# bd2_redraw.net
KiCad netlist of a schematic drawn in EAGLE
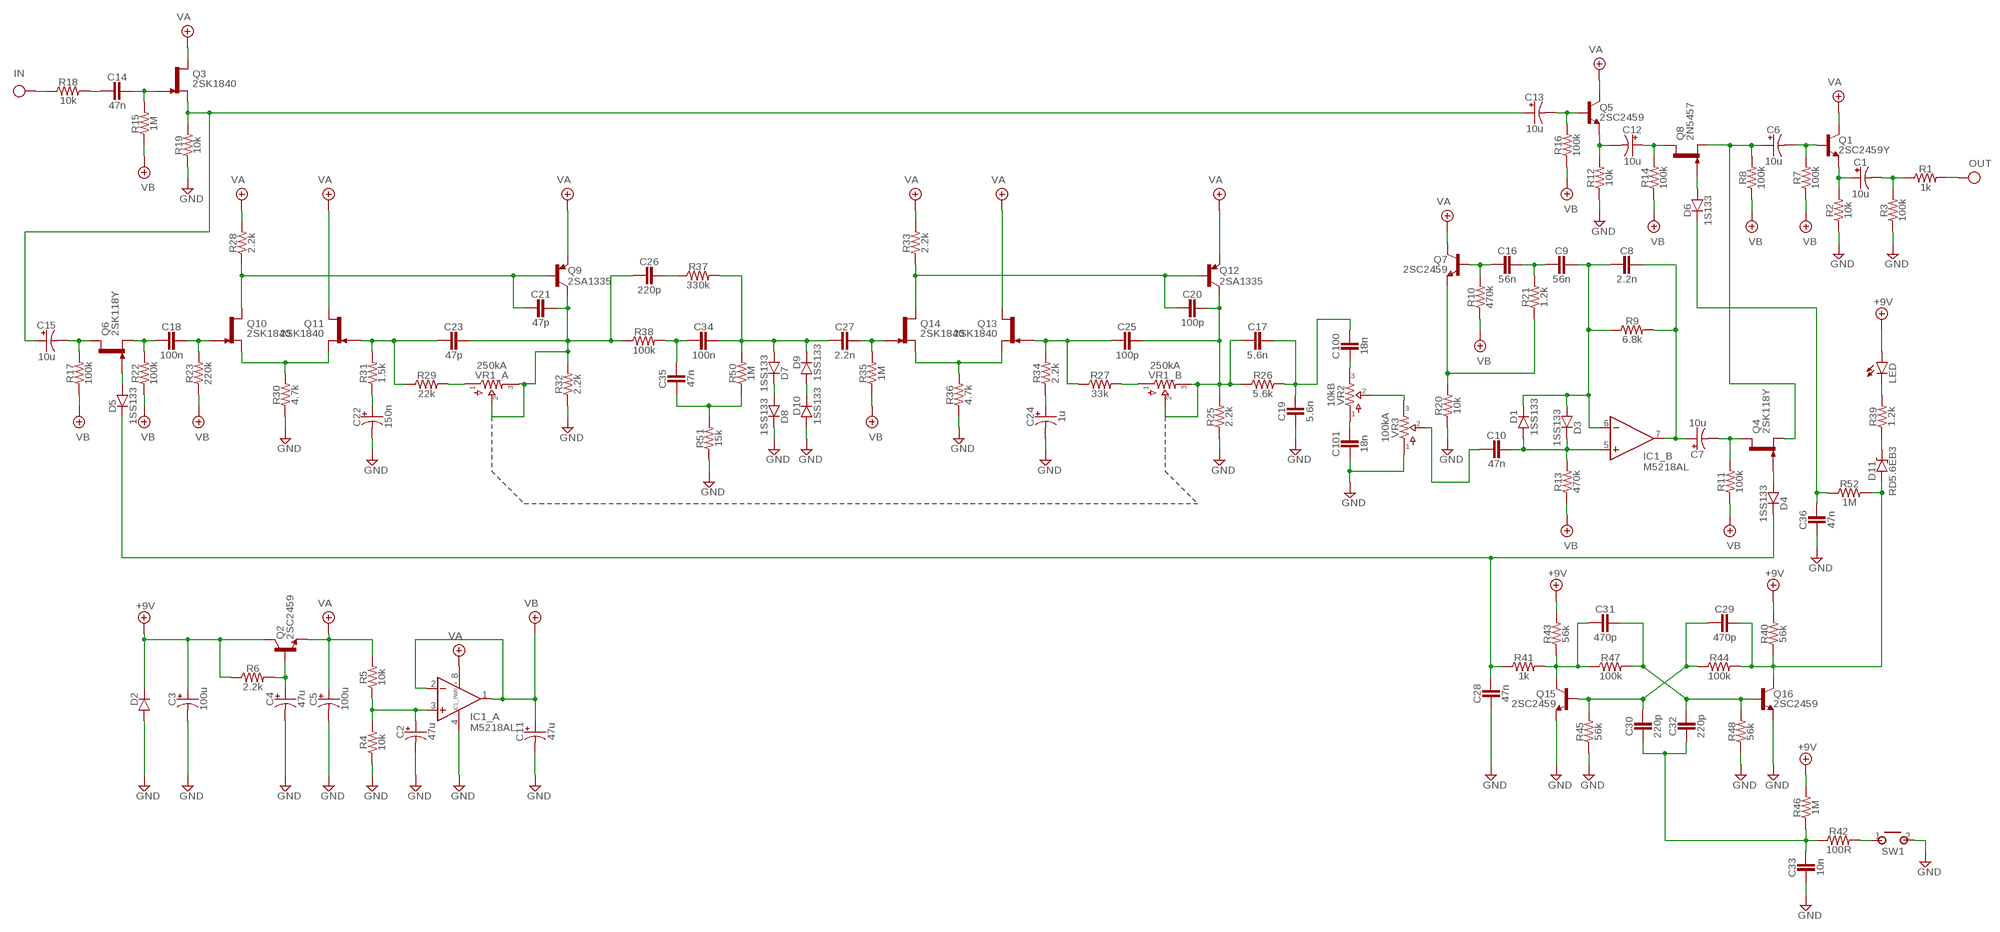
[diagram p0: schematic, sheet 1]

(export (version "E")
  (design (tool "Eeschema 10.0.6"))
  (components
    (comp (ref "C1")
      (value "10u")
      (footprint "eagle-import:040_020")
      (libsource (lib "eagle-import") (part "0400"))
    )
    (comp (ref "C2")
      (value "47u")
      (footprint "eagle-import:040_020")
      (libsource (lib "eagle-import") (part "0400"))
    )
    (comp (ref "C3")
      (value "100u")
      (footprint "eagle-import:040_020")
      (libsource (lib "eagle-import") (part "0400"))
    )
    (comp (ref "C4")
      (value "47u")
      (footprint "eagle-import:040_020")
      (libsource (lib "eagle-import") (part "0400"))
    )
    (comp (ref "C5")
      (value "100u")
      (footprint "eagle-import:040_020")
      (libsource (lib "eagle-import") (part "0400"))
    )
    (comp (ref "C6")
      (value "10u")
      (footprint "eagle-import:040_020")
      (libsource (lib "eagle-import") (part "0400"))
    )
    (comp (ref "C7")
      (value "10u")
      (footprint "eagle-import:040_020")
      (libsource (lib "eagle-import") (part "0400"))
    )
    (comp (ref "C8")
      (value "2.2n")
      (footprint "eagle-import:BOX_SMALL")
      (libsource (lib "eagle-import") (part "CER/FILMBOX.1"))
    )
    (comp (ref "C9")
      (value "56n")
      (footprint "eagle-import:BOX_SMALL")
      (libsource (lib "eagle-import") (part "CER/FILMBOX.1"))
    )
    (comp (ref "C10")
      (value "47n")
      (footprint "eagle-import:BOX_SMALL")
      (libsource (lib "eagle-import") (part "CER/FILMBOX.1"))
    )
    (comp (ref "C11")
      (value "47u")
      (footprint "eagle-import:040_020")
      (libsource (lib "eagle-import") (part "0400"))
    )
    (comp (ref "C12")
      (value "10u")
      (footprint "eagle-import:040_020")
      (libsource (lib "eagle-import") (part "0400"))
    )
    (comp (ref "C13")
      (value "10u")
      (footprint "eagle-import:040_020")
      (libsource (lib "eagle-import") (part "0400"))
    )
    (comp (ref "C14")
      (value "47n")
      (footprint "eagle-import:BOX_SMALL")
      (libsource (lib "eagle-import") (part "CER/FILMBOX.1"))
    )
    (comp (ref "C15")
      (value "10u")
      (footprint "eagle-import:040_020")
      (libsource (lib "eagle-import") (part "0400"))
    )
    (comp (ref "C16")
      (value "56n")
      (footprint "eagle-import:BOX_SMALL")
      (libsource (lib "eagle-import") (part "CER/FILMBOX.1"))
    )
    (comp (ref "C17")
      (value "5.6n")
      (footprint "eagle-import:BOX_SMALL")
      (libsource (lib "eagle-import") (part "CER/FILMBOX.1"))
    )
    (comp (ref "C18")
      (value "100n")
      (footprint "eagle-import:BOX_SMALL")
      (libsource (lib "eagle-import") (part "CER/FILMBOX.1"))
    )
    (comp (ref "C19")
      (value "5.6n")
      (footprint "eagle-import:BOX_SMALL")
      (libsource (lib "eagle-import") (part "CER/FILMBOX.1"))
    )
    (comp (ref "C20")
      (value "100p")
      (footprint "eagle-import:BOX_SMALL")
      (libsource (lib "eagle-import") (part "CER/FILMBOX.1"))
    )
    (comp (ref "C21")
      (value "47p")
      (footprint "eagle-import:BOX_SMALL")
      (libsource (lib "eagle-import") (part "CER/FILMBOX.1"))
    )
    (comp (ref "C22")
      (value "150n")
      (footprint "eagle-import:040_020")
      (libsource (lib "eagle-import") (part "0400"))
    )
    (comp (ref "C23")
      (value "47p")
      (footprint "eagle-import:BOX_SMALL")
      (libsource (lib "eagle-import") (part "CER/FILMBOX.1"))
    )
    (comp (ref "C24")
      (value "1u")
      (footprint "eagle-import:040_020")
      (libsource (lib "eagle-import") (part "0400"))
    )
    (comp (ref "C25")
      (value "100p")
      (footprint "eagle-import:BOX_SMALL")
      (libsource (lib "eagle-import") (part "CER/FILMBOX.1"))
    )
    (comp (ref "C26")
      (value "220p")
      (footprint "eagle-import:BOX_SMALL")
      (libsource (lib "eagle-import") (part "CER/FILMBOX.1"))
    )
    (comp (ref "C27")
      (value "2.2n")
      (footprint "eagle-import:BOX_SMALL")
      (libsource (lib "eagle-import") (part "CER/FILMBOX.1"))
    )
    (comp (ref "C28")
      (value "47n")
      (footprint "eagle-import:BOX_SMALL")
      (libsource (lib "eagle-import") (part "CER/FILMBOX.1"))
    )
    (comp (ref "C29")
      (value "470p")
      (footprint "eagle-import:BOX_SMALL")
      (libsource (lib "eagle-import") (part "CER/FILMBOX.1"))
    )
    (comp (ref "C30")
      (value "220p")
      (footprint "eagle-import:BOX_SMALL")
      (libsource (lib "eagle-import") (part "CER/FILMBOX.1"))
    )
    (comp (ref "C31")
      (value "470p")
      (footprint "eagle-import:BOX_SMALL")
      (libsource (lib "eagle-import") (part "CER/FILMBOX.1"))
    )
    (comp (ref "C32")
      (value "220p")
      (footprint "eagle-import:BOX_SMALL")
      (libsource (lib "eagle-import") (part "CER/FILMBOX.1"))
    )
    (comp (ref "C33")
      (value "10n")
      (footprint "eagle-import:BOX_SMALL")
      (libsource (lib "eagle-import") (part "CER/FILMBOX.1"))
    )
    (comp (ref "C34")
      (value "100n")
      (footprint "eagle-import:BOX_SMALL")
      (libsource (lib "eagle-import") (part "CER/FILMBOX.1"))
    )
    (comp (ref "C35")
      (value "47n")
      (footprint "eagle-import:BOX_SMALL")
      (libsource (lib "eagle-import") (part "CER/FILMBOX.1"))
    )
    (comp (ref "C36")
      (value "47n")
      (footprint "eagle-import:BOX_SMALL")
      (libsource (lib "eagle-import") (part "CER/FILMBOX.1"))
    )
    (comp (ref "C100")
      (value "18n")
      (footprint "eagle-import:BOX_SMALL")
      (libsource (lib "eagle-import") (part "CER/FILMBOX.1"))
    )
    (comp (ref "C101")
      (value "18n")
      (footprint "eagle-import:BOX_SMALL")
      (libsource (lib "eagle-import") (part "CER/FILMBOX.1"))
    )
    (comp (ref "D1")
      (value "1SS133")
      (footprint "eagle-import:DO41-2")
      (libsource (lib "eagle-import") (part "DO41.2"))
    )
    (comp (ref "D2")
      (value "DO41.2")
      (footprint "eagle-import:DO41-2")
      (libsource (lib "eagle-import") (part "DO41.2"))
    )
    (comp (ref "D3")
      (value "1SS133")
      (footprint "eagle-import:DO41-2")
      (libsource (lib "eagle-import") (part "DO41.2"))
    )
    (comp (ref "D4")
      (value "1SS133")
      (footprint "eagle-import:DO41-2")
      (libsource (lib "eagle-import") (part "DO41.2"))
    )
    (comp (ref "D5")
      (value "1SS133")
      (footprint "eagle-import:DO41-2")
      (libsource (lib "eagle-import") (part "DO41.2"))
    )
    (comp (ref "D6")
      (value "1S133")
      (footprint "eagle-import:DO41-2")
      (libsource (lib "eagle-import") (part "DO41.2"))
    )
    (comp (ref "D7")
      (value "1SS133")
      (footprint "eagle-import:DO41-2")
      (libsource (lib "eagle-import") (part "DO41.2"))
    )
    (comp (ref "D8")
      (value "1SS133")
      (footprint "eagle-import:DO41-2")
      (libsource (lib "eagle-import") (part "DO41.2"))
    )
    (comp (ref "D9")
      (value "1SS133")
      (footprint "eagle-import:DO41-2")
      (libsource (lib "eagle-import") (part "DO41.2"))
    )
    (comp (ref "D10")
      (value "1SS133")
      (footprint "eagle-import:DO41-2")
      (libsource (lib "eagle-import") (part "DO41.2"))
    )
    (comp (ref "D11")
      (value "RD5.6EB3")
      (footprint "eagle-import:DO41-2")
      (libsource (lib "eagle-import") (part "ZENER.2"))
    )
    (comp (ref "IC1")
      (value "M5218AL")
      (footprint "eagle-import:DIL0")
      (libsource (lib "eagle-import") (part "DUALTH"))
    )
    (comp (ref "LED")
      (value "LED")
      (footprint "eagle-import:3MM_D")
      (libsource (lib "eagle-import") (part "LED"))
    )
    (comp (ref "Q1")
      (value "2SC2459Y")
      (footprint "eagle-import:TO92-")
      (libsource (lib "eagle-import") (part "2N3904"))
    )
    (comp (ref "Q2")
      (value "2SC2459")
      (footprint "eagle-import:TO92-")
      (libsource (lib "eagle-import") (part "2N3904"))
    )
    (comp (ref "Q3")
      (value "2SK1840")
      (footprint "eagle-import:TO92-")
      (libsource (lib "eagle-import") (part "2N5457"))
    )
    (comp (ref "Q4")
      (value "2SK118Y")
      (footprint "eagle-import:TO92-")
      (libsource (lib "eagle-import") (part "2N5457"))
    )
    (comp (ref "Q5")
      (value "2SC2459")
      (footprint "eagle-import:TO92-")
      (libsource (lib "eagle-import") (part "2N3904"))
    )
    (comp (ref "Q6")
      (value "2SK118Y")
      (footprint "eagle-import:TO92-")
      (libsource (lib "eagle-import") (part "2N5457"))
    )
    (comp (ref "Q7")
      (value "2SC2459")
      (footprint "eagle-import:TO92-")
      (libsource (lib "eagle-import") (part "2N3904"))
    )
    (comp (ref "Q8")
      (value "2N5457")
      (footprint "eagle-import:TO92-")
      (libsource (lib "eagle-import") (part "2N5457"))
    )
    (comp (ref "Q9")
      (value "2SA1335")
      (footprint "eagle-import:TO92-")
      (libsource (lib "eagle-import") (part "2N3906-"))
    )
    (comp (ref "Q10")
      (value "2SK1840")
      (footprint "eagle-import:TO92-")
      (libsource (lib "eagle-import") (part "2N5457"))
    )
    (comp (ref "Q11")
      (value "2SK1840")
      (footprint "eagle-import:TO92-")
      (libsource (lib "eagle-import") (part "2N5457"))
    )
    (comp (ref "Q12")
      (value "2SA1335")
      (footprint "eagle-import:TO92-")
      (libsource (lib "eagle-import") (part "2N3906-"))
    )
    (comp (ref "Q13")
      (value "2SK1840")
      (footprint "eagle-import:TO92-")
      (libsource (lib "eagle-import") (part "2N5457"))
    )
    (comp (ref "Q14")
      (value "2SK1840")
      (footprint "eagle-import:TO92-")
      (libsource (lib "eagle-import") (part "2N5457"))
    )
    (comp (ref "Q15")
      (value "2SC2459")
      (footprint "eagle-import:TO92-")
      (libsource (lib "eagle-import") (part "2N3904"))
    )
    (comp (ref "Q16")
      (value "2SC2459")
      (footprint "eagle-import:TO92-")
      (libsource (lib "eagle-import") (part "2N3904"))
    )
    (comp (ref "R1")
      (value "1k")
      (footprint "eagle-import:R0207_3")
      (libsource (lib "eagle-import") (part "R_.3B"))
    )
    (comp (ref "R2")
      (value "10k")
      (footprint "eagle-import:R0207_3")
      (libsource (lib "eagle-import") (part "R_.3B"))
    )
    (comp (ref "R3")
      (value "100k")
      (footprint "eagle-import:R0207_3")
      (libsource (lib "eagle-import") (part "R_.3B"))
    )
    (comp (ref "R4")
      (value "10k")
      (footprint "eagle-import:R0207_3")
      (libsource (lib "eagle-import") (part "R_.3B"))
    )
    (comp (ref "R5")
      (value "10k")
      (footprint "eagle-import:R0207_3")
      (libsource (lib "eagle-import") (part "R_.3B"))
    )
    (comp (ref "R6")
      (value "2.2k")
      (footprint "eagle-import:R0207_3")
      (libsource (lib "eagle-import") (part "R_.3B"))
    )
    (comp (ref "R7")
      (value "100k")
      (footprint "eagle-import:R0207_3")
      (libsource (lib "eagle-import") (part "R_.3B"))
    )
    (comp (ref "R8")
      (value "100k")
      (footprint "eagle-import:R0207_3")
      (libsource (lib "eagle-import") (part "R_.3B"))
    )
    (comp (ref "R9")
      (value "6.8k")
      (footprint "eagle-import:R0207_3")
      (libsource (lib "eagle-import") (part "R_.3B"))
    )
    (comp (ref "R10")
      (value "470k")
      (footprint "eagle-import:R0207_3")
      (libsource (lib "eagle-import") (part "R_.3B"))
    )
    (comp (ref "R11")
      (value "100k")
      (footprint "eagle-import:R0207_3")
      (libsource (lib "eagle-import") (part "R_.3B"))
    )
    (comp (ref "R12")
      (value "10k")
      (footprint "eagle-import:R0207_3")
      (libsource (lib "eagle-import") (part "R_.3B"))
    )
    (comp (ref "R13")
      (value "470k")
      (footprint "eagle-import:R0207_3")
      (libsource (lib "eagle-import") (part "R_.3B"))
    )
    (comp (ref "R14")
      (value "100k")
      (footprint "eagle-import:R0207_3")
      (libsource (lib "eagle-import") (part "R_.3B"))
    )
    (comp (ref "R15")
      (value "1M")
      (footprint "eagle-import:R0207_3")
      (libsource (lib "eagle-import") (part "R_.3B"))
    )
    (comp (ref "R16")
      (value "100k")
      (footprint "eagle-import:R0207_3")
      (libsource (lib "eagle-import") (part "R_.3B"))
    )
    (comp (ref "R17")
      (value "100k")
      (footprint "eagle-import:R0207_3")
      (libsource (lib "eagle-import") (part "R_.3B"))
    )
    (comp (ref "R18")
      (value "10k")
      (footprint "eagle-import:R0207_3")
      (libsource (lib "eagle-import") (part "R_.3B"))
    )
    (comp (ref "R19")
      (value "10k")
      (footprint "eagle-import:R0207_3")
      (libsource (lib "eagle-import") (part "R_.3B"))
    )
    (comp (ref "R20")
      (value "10k")
      (footprint "eagle-import:R0207_3")
      (libsource (lib "eagle-import") (part "R_.3B"))
    )
    (comp (ref "R21")
      (value "1.2k")
      (footprint "eagle-import:R0207_3")
      (libsource (lib "eagle-import") (part "R_.3B"))
    )
    (comp (ref "R22")
      (value "100k")
      (footprint "eagle-import:R0207_3")
      (libsource (lib "eagle-import") (part "R_.3B"))
    )
    (comp (ref "R23")
      (value "220k")
      (footprint "eagle-import:R0207_3")
      (libsource (lib "eagle-import") (part "R_.3B"))
    )
    (comp (ref "R25")
      (value "2.2k")
      (footprint "eagle-import:R0207_3")
      (libsource (lib "eagle-import") (part "R_.3B"))
    )
    (comp (ref "R26")
      (value "5.6k")
      (footprint "eagle-import:R0207_3")
      (libsource (lib "eagle-import") (part "R_.3B"))
    )
    (comp (ref "R27")
      (value "33k")
      (footprint "eagle-import:R0207_3")
      (libsource (lib "eagle-import") (part "R_.3B"))
    )
    (comp (ref "R28")
      (value "2.2k")
      (footprint "eagle-import:R0207_3")
      (libsource (lib "eagle-import") (part "R_.3B"))
    )
    (comp (ref "R29")
      (value "22k")
      (footprint "eagle-import:R0207_3")
      (libsource (lib "eagle-import") (part "R_.3B"))
    )
    (comp (ref "R30")
      (value "4.7k")
      (footprint "eagle-import:R0207_3")
      (libsource (lib "eagle-import") (part "R_.3B"))
    )
    (comp (ref "R31")
      (value "1.5k")
      (footprint "eagle-import:R0207_3")
      (libsource (lib "eagle-import") (part "R_.3B"))
    )
    (comp (ref "R32")
      (value "2.2k")
      (footprint "eagle-import:R0207_3")
      (libsource (lib "eagle-import") (part "R_.3B"))
    )
    (comp (ref "R33")
      (value "2.2k")
      (footprint "eagle-import:R0207_3")
      (libsource (lib "eagle-import") (part "R_.3B"))
    )
    (comp (ref "R34")
      (value "2.2k")
      (footprint "eagle-import:R0207_3")
      (libsource (lib "eagle-import") (part "R_.3B"))
    )
    (comp (ref "R35")
      (value "1M")
      (footprint "eagle-import:R0207_3")
      (libsource (lib "eagle-import") (part "R_.3B"))
    )
    (comp (ref "R36")
      (value "4.7k")
      (footprint "eagle-import:R0207_3")
      (libsource (lib "eagle-import") (part "R_.3B"))
    )
    (comp (ref "R37")
      (value "330k")
      (footprint "eagle-import:R0207_3")
      (libsource (lib "eagle-import") (part "R_.3B"))
    )
    (comp (ref "R38")
      (value "100k")
      (footprint "eagle-import:R0207_3")
      (libsource (lib "eagle-import") (part "R_.3B"))
    )
    (comp (ref "R39")
      (value "1.2k")
      (footprint "eagle-import:R0207_3")
      (libsource (lib "eagle-import") (part "R_.3B"))
    )
    (comp (ref "R40")
      (value "56k")
      (footprint "eagle-import:R0207_3")
      (libsource (lib "eagle-import") (part "R_.3B"))
    )
    (comp (ref "R41")
      (value "1k")
      (footprint "eagle-import:R0207_3")
      (libsource (lib "eagle-import") (part "R_.3B"))
    )
    (comp (ref "R42")
      (value "100R")
      (footprint "eagle-import:R0207_3")
      (libsource (lib "eagle-import") (part "R_.3B"))
    )
    (comp (ref "R43")
      (value "56k")
      (footprint "eagle-import:R0207_3")
      (libsource (lib "eagle-import") (part "R_.3B"))
    )
    (comp (ref "R44")
      (value "100k")
      (footprint "eagle-import:R0207_3")
      (libsource (lib "eagle-import") (part "R_.3B"))
    )
    (comp (ref "R45")
      (value "56k")
      (footprint "eagle-import:R0207_3")
      (libsource (lib "eagle-import") (part "R_.3B"))
    )
    (comp (ref "R46")
      (value "1M")
      (footprint "eagle-import:R0207_3")
      (libsource (lib "eagle-import") (part "R_.3B"))
    )
    (comp (ref "R47")
      (value "100k")
      (footprint "eagle-import:R0207_3")
      (libsource (lib "eagle-import") (part "R_.3B"))
    )
    (comp (ref "R48")
      (value "56k")
      (footprint "eagle-import:R0207_3")
      (libsource (lib "eagle-import") (part "R_.3B"))
    )
    (comp (ref "R50")
      (value "1M")
      (footprint "eagle-import:R0207_3")
      (libsource (lib "eagle-import") (part "R_.3B"))
    )
    (comp (ref "R51")
      (value "15k")
      (footprint "eagle-import:R0207_3")
      (libsource (lib "eagle-import") (part "R_.3B"))
    )
    (comp (ref "R52")
      (value "1M")
      (footprint "eagle-import:R0207_3")
      (libsource (lib "eagle-import") (part "R_.3B"))
    )
    (comp (ref "SW1")
      (value "MOMENTARY")
      (footprint "eagle-import:SPST")
      (libsource (lib "eagle-import") (part "MOMENTARY"))
    )
    (comp (ref "VR1")
      (value "250kA")
      (footprint "eagle-import:16MM_DUAL")
      (libsource (lib "eagle-import") (part "DUALGANG16MM_DUAL"))
    )
    (comp (ref "VR2")
      (value "10kB")
      (footprint "eagle-import:16MM")
      (libsource (lib "eagle-import") (part "POTS16MM"))
    )
    (comp (ref "VR3")
      (value "100kA")
      (footprint "eagle-import:16MM")
      (libsource (lib "eagle-import") (part "POTS16MM"))
    )
  )
  (nets
    (net (code "1") (name "+9V") (class "Default")
      (node (ref "C3") (pin "+") (pinfunction "+_+") (pintype "passive"))
      (node (ref "D2") (pin "C") (pinfunction "C_C") (pintype "passive"))
      (node (ref "LED") (pin "ANODE") (pinfunction "A_ANODE") (pintype "passive"))
      (node (ref "Q2") (pin "1") (pinfunction "C_1") (pintype "passive"))
      (node (ref "R40") (pin "2") (pinfunction "2_2") (pintype "passive"))
      (node (ref "R43") (pin "2") (pinfunction "2_2") (pintype "passive"))
      (node (ref "R46") (pin "2") (pinfunction "2_2") (pintype "passive"))
      (node (ref "R6") (pin "1") (pinfunction "1_1") (pintype "passive"))
    )
    (net (code "2") (name "GND") (class "Default")
      (node (ref "C101") (pin "2") (pinfunction "2_2") (pintype "passive"))
      (node (ref "C11") (pin "-") (pinfunction "-_-") (pintype "passive"))
      (node (ref "C19") (pin "2") (pinfunction "2_2") (pintype "passive"))
      (node (ref "C2") (pin "-") (pinfunction "-_-") (pintype "passive"))
      (node (ref "C22") (pin "-") (pinfunction "-_-") (pintype "passive"))
      (node (ref "C24") (pin "-") (pinfunction "-_-") (pintype "passive"))
      (node (ref "C28") (pin "2") (pinfunction "2_2") (pintype "passive"))
      (node (ref "C3") (pin "-") (pinfunction "-_-") (pintype "passive"))
      (node (ref "C33") (pin "2") (pinfunction "2_2") (pintype "passive"))
      (node (ref "C36") (pin "2") (pinfunction "2_2") (pintype "passive"))
      (node (ref "C4") (pin "-") (pinfunction "-_-") (pintype "passive"))
      (node (ref "C5") (pin "-") (pinfunction "-_-") (pintype "passive"))
      (node (ref "D10") (pin "A") (pinfunction "A_A") (pintype "passive"))
      (node (ref "D2") (pin "A") (pinfunction "A_A") (pintype "passive"))
      (node (ref "D8") (pin "C") (pinfunction "C_C") (pintype "passive"))
      (node (ref "IC1") (pin "4") (pinfunction "V-_4") (pintype "power_in"))
      (node (ref "Q15") (pin "3") (pinfunction "E_3") (pintype "passive"))
      (node (ref "Q16") (pin "3") (pinfunction "E_3") (pintype "passive"))
      (node (ref "R12") (pin "1") (pinfunction "1_1") (pintype "passive"))
      (node (ref "R19") (pin "1") (pinfunction "1_1") (pintype "passive"))
      (node (ref "R2") (pin "1") (pinfunction "1_1") (pintype "passive"))
      (node (ref "R20") (pin "1") (pinfunction "1_1") (pintype "passive"))
      (node (ref "R25") (pin "1") (pinfunction "1_1") (pintype "passive"))
      (node (ref "R3") (pin "1") (pinfunction "1_1") (pintype "passive"))
      (node (ref "R30") (pin "1") (pinfunction "1_1") (pintype "passive"))
      (node (ref "R32") (pin "1") (pinfunction "1_1") (pintype "passive"))
      (node (ref "R36") (pin "1") (pinfunction "1_1") (pintype "passive"))
      (node (ref "R4") (pin "1") (pinfunction "1_1") (pintype "passive"))
      (node (ref "R45") (pin "1") (pinfunction "1_1") (pintype "passive"))
      (node (ref "R48") (pin "1") (pinfunction "1_1") (pintype "passive"))
      (node (ref "R51") (pin "1") (pinfunction "1_1") (pintype "passive"))
      (node (ref "SW1") (pin "2") (pinfunction "S_2") (pintype "passive"))
      (node (ref "VR3") (pin "1") (pinfunction "1_1") (pintype "passive"))
    )
    (net (code "3") (name "IN") (class "Default")
      (node (ref "R18") (pin "1") (pinfunction "1_1") (pintype "passive"))
    )
    (net (code "4") (name "Net-(C1-Pad-)") (class "Default")
      (node (ref "C1") (pin "-") (pinfunction "-_-") (pintype "passive"))
      (node (ref "R1") (pin "1") (pinfunction "1_1") (pintype "passive"))
      (node (ref "R3") (pin "2") (pinfunction "2_2") (pintype "passive"))
    )
    (net (code "5") (name "Net-(C10-Pad2)") (class "Default")
      (node (ref "C10") (pin "2") (pinfunction "2_2") (pintype "passive"))
      (node (ref "VR3") (pin "2") (pinfunction "2_2") (pintype "passive"))
    )
    (net (code "6") (name "Net-(C14-Pad2)") (class "Default")
      (node (ref "C14") (pin "2") (pinfunction "2_2") (pintype "passive"))
      (node (ref "R18") (pin "2") (pinfunction "2_2") (pintype "passive"))
    )
    (net (code "7") (name "Net-(C16-Pad1)") (class "Default")
      (node (ref "C16") (pin "1") (pinfunction "1_1") (pintype "passive"))
      (node (ref "C9") (pin "2") (pinfunction "2_2") (pintype "passive"))
      (node (ref "R21") (pin "2") (pinfunction "2_2") (pintype "passive"))
    )
    (net (code "8") (name "Net-(C22-Pad+)") (class "Default")
      (node (ref "C22") (pin "+") (pinfunction "+_+") (pintype "passive"))
      (node (ref "R31") (pin "1") (pinfunction "1_1") (pintype "passive"))
    )
    (net (code "9") (name "Net-(C24-Pad+)") (class "Default")
      (node (ref "C24") (pin "+") (pinfunction "+_+") (pintype "passive"))
      (node (ref "R34") (pin "1") (pinfunction "1_1") (pintype "passive"))
    )
    (net (code "10") (name "Net-(C26-Pad1)") (class "Default")
      (node (ref "C26") (pin "1") (pinfunction "1_1") (pintype "passive"))
      (node (ref "R37") (pin "1") (pinfunction "1_1") (pintype "passive"))
    )
    (net (code "11") (name "Net-(C27-Pad2)") (class "Default")
      (node (ref "C27") (pin "2") (pinfunction "2_2") (pintype "passive"))
      (node (ref "C34") (pin "1") (pinfunction "1_1") (pintype "passive"))
      (node (ref "D7") (pin "A") (pinfunction "A_A") (pintype "passive"))
      (node (ref "D9") (pin "C") (pinfunction "C_C") (pintype "passive"))
      (node (ref "R37") (pin "2") (pinfunction "2_2") (pintype "passive"))
      (node (ref "R50") (pin "2") (pinfunction "2_2") (pintype "passive"))
    )
    (net (code "12") (name "Net-(C28-Pad1)") (class "Default")
      (node (ref "C28") (pin "1") (pinfunction "1_1") (pintype "passive"))
      (node (ref "D4") (pin "C") (pinfunction "C_C") (pintype "passive"))
      (node (ref "D5") (pin "C") (pinfunction "C_C") (pintype "passive"))
      (node (ref "R41") (pin "1") (pinfunction "1_1") (pintype "passive"))
    )
    (net (code "13") (name "Net-(C30-Pad2)") (class "Default")
      (node (ref "C30") (pin "2") (pinfunction "2_2") (pintype "passive"))
      (node (ref "C32") (pin "2") (pinfunction "2_2") (pintype "passive"))
      (node (ref "C33") (pin "1") (pinfunction "1_1") (pintype "passive"))
      (node (ref "R42") (pin "1") (pinfunction "1_1") (pintype "passive"))
      (node (ref "R46") (pin "1") (pinfunction "1_1") (pintype "passive"))
    )
    (net (code "14") (name "Net-(C34-Pad2)") (class "Default")
      (node (ref "C34") (pin "2") (pinfunction "2_2") (pintype "passive"))
      (node (ref "C35") (pin "1") (pinfunction "1_1") (pintype "passive"))
      (node (ref "R38") (pin "2") (pinfunction "2_2") (pintype "passive"))
    )
    (net (code "15") (name "Net-(C35-Pad2)") (class "Default")
      (node (ref "C35") (pin "2") (pinfunction "2_2") (pintype "passive"))
      (node (ref "R50") (pin "1") (pinfunction "1_1") (pintype "passive"))
      (node (ref "R51") (pin "2") (pinfunction "2_2") (pintype "passive"))
    )
    (net (code "16") (name "Net-(C36-Pad1)") (class "Default")
      (node (ref "C36") (pin "1") (pinfunction "1_1") (pintype "passive"))
      (node (ref "D6") (pin "C") (pinfunction "C_C") (pintype "passive"))
      (node (ref "R52") (pin "1") (pinfunction "1_1") (pintype "passive"))
    )
    (net (code "17") (name "Net-(C100-Pad1)") (class "Default")
      (node (ref "C100") (pin "1") (pinfunction "1_1") (pintype "passive"))
      (node (ref "C17") (pin "1") (pinfunction "1_1") (pintype "passive"))
      (node (ref "C19") (pin "1") (pinfunction "1_1") (pintype "passive"))
      (node (ref "R26") (pin "2") (pinfunction "2_2") (pintype "passive"))
    )
    (net (code "18") (name "Net-(C100-Pad2)") (class "Default")
      (node (ref "C100") (pin "2") (pinfunction "2_2") (pintype "passive"))
      (node (ref "VR2") (pin "3") (pinfunction "3_3") (pintype "passive"))
    )
    (net (code "19") (name "Net-(C101-Pad1)") (class "Default")
      (node (ref "C101") (pin "1") (pinfunction "1_1") (pintype "passive"))
      (node (ref "VR2") (pin "1") (pinfunction "1_1") (pintype "passive"))
    )
    (net (code "20") (name "Net-(D7-PadC)") (class "Default")
      (node (ref "D7") (pin "C") (pinfunction "C_C") (pintype "passive"))
      (node (ref "D8") (pin "A") (pinfunction "A_A") (pintype "passive"))
    )
    (net (code "21") (name "Net-(D10-PadC)") (class "Default")
      (node (ref "D10") (pin "C") (pinfunction "C_C") (pintype "passive"))
      (node (ref "D9") (pin "A") (pinfunction "A_A") (pintype "passive"))
    )
    (net (code "22") (name "Net-(D11-PadC)") (class "Default")
      (node (ref "D11") (pin "C") (pinfunction "C_C") (pintype "passive"))
      (node (ref "R39") (pin "1") (pinfunction "1_1") (pintype "passive"))
    )
    (net (code "23") (name "Net-(IC1A-+IN)") (class "Default")
      (node (ref "C2") (pin "+") (pinfunction "+_+") (pintype "passive"))
      (node (ref "IC1") (pin "3") (pinfunction "+IN_3") (pintype "input"))
      (node (ref "R4") (pin "2") (pinfunction "2_2") (pintype "passive"))
      (node (ref "R5") (pin "1") (pinfunction "1_1") (pintype "passive"))
    )
    (net (code "24") (name "Net-(IC1B-+IN)") (class "Default")
      (node (ref "C10") (pin "1") (pinfunction "1_1") (pintype "passive"))
      (node (ref "D1") (pin "A") (pinfunction "A_A") (pintype "passive"))
      (node (ref "D3") (pin "C") (pinfunction "C_C") (pintype "passive"))
      (node (ref "IC1") (pin "5") (pinfunction "+IN_5") (pintype "input"))
      (node (ref "R13") (pin "2") (pinfunction "2_2") (pintype "passive"))
    )
    (net (code "25") (name "Net-(IC1B--IN)") (class "Default")
      (node (ref "C8") (pin "2") (pinfunction "2_2") (pintype "passive"))
      (node (ref "C9") (pin "1") (pinfunction "1_1") (pintype "passive"))
      (node (ref "D1") (pin "C") (pinfunction "C_C") (pintype "passive"))
      (node (ref "D3") (pin "A") (pinfunction "A_A") (pintype "passive"))
      (node (ref "IC1") (pin "6") (pinfunction "-IN_6") (pintype "input"))
      (node (ref "R9") (pin "1") (pinfunction "1_1") (pintype "passive"))
    )
    (net (code "26") (name "Net-(IC1B-OUT)") (class "Default")
      (node (ref "C7") (pin "+") (pinfunction "+_+") (pintype "passive"))
      (node (ref "C8") (pin "1") (pinfunction "1_1") (pintype "passive"))
      (node (ref "IC1") (pin "7") (pinfunction "OUT_7") (pintype "output"))
      (node (ref "R9") (pin "2") (pinfunction "2_2") (pintype "passive"))
    )
    (net (code "27") (name "Net-(LED-C)") (class "Default")
      (node (ref "LED") (pin "P$1") (pinfunction "C_P$1") (pintype "passive"))
      (node (ref "R39") (pin "2") (pinfunction "2_2") (pintype "passive"))
    )
    (net (code "28") (name "Net-(Q1-B)") (class "Default")
      (node (ref "C6") (pin "-") (pinfunction "-_-") (pintype "passive"))
      (node (ref "Q1") (pin "2") (pinfunction "B_2") (pintype "passive"))
      (node (ref "R7") (pin "2") (pinfunction "2_2") (pintype "passive"))
    )
    (net (code "29") (name "Net-(Q1-E)") (class "Default")
      (node (ref "C1") (pin "+") (pinfunction "+_+") (pintype "passive"))
      (node (ref "Q1") (pin "3") (pinfunction "E_3") (pintype "passive"))
      (node (ref "R2") (pin "2") (pinfunction "2_2") (pintype "passive"))
    )
    (net (code "30") (name "Net-(Q2-B)") (class "Default")
      (node (ref "C4") (pin "+") (pinfunction "+_+") (pintype "passive"))
      (node (ref "Q2") (pin "2") (pinfunction "B_2") (pintype "passive"))
      (node (ref "R6") (pin "2") (pinfunction "2_2") (pintype "passive"))
    )
    (net (code "31") (name "Net-(Q3-G)") (class "Default")
      (node (ref "C14") (pin "1") (pinfunction "1_1") (pintype "passive"))
      (node (ref "Q3") (pin "1") (pinfunction "G_1") (pintype "passive"))
      (node (ref "R15") (pin "2") (pinfunction "2_2") (pintype "passive"))
    )
    (net (code "32") (name "Net-(Q3-S)") (class "Default")
      (node (ref "C13") (pin "+") (pinfunction "+_+") (pintype "passive"))
      (node (ref "C15") (pin "+") (pinfunction "+_+") (pintype "passive"))
      (node (ref "Q3") (pin "2") (pinfunction "S_2") (pintype "passive"))
      (node (ref "R19") (pin "2") (pinfunction "2_2") (pintype "passive"))
    )
    (net (code "33") (name "Net-(Q4-D)") (class "Default")
      (node (ref "C7") (pin "-") (pinfunction "-_-") (pintype "passive"))
      (node (ref "Q4") (pin "3") (pinfunction "D_3") (pintype "passive"))
      (node (ref "R11") (pin "2") (pinfunction "2_2") (pintype "passive"))
    )
    (net (code "34") (name "Net-(Q4-G)") (class "Default")
      (node (ref "D4") (pin "A") (pinfunction "A_A") (pintype "passive"))
      (node (ref "Q4") (pin "1") (pinfunction "G_1") (pintype "passive"))
    )
    (net (code "35") (name "Net-(Q4-S)") (class "Default")
      (node (ref "C6") (pin "+") (pinfunction "+_+") (pintype "passive"))
      (node (ref "Q4") (pin "2") (pinfunction "S_2") (pintype "passive"))
      (node (ref "Q8") (pin "2") (pinfunction "S_2") (pintype "passive"))
      (node (ref "R8") (pin "2") (pinfunction "2_2") (pintype "passive"))
    )
    (net (code "36") (name "Net-(Q5-B)") (class "Default")
      (node (ref "C13") (pin "-") (pinfunction "-_-") (pintype "passive"))
      (node (ref "Q5") (pin "2") (pinfunction "B_2") (pintype "passive"))
      (node (ref "R16") (pin "2") (pinfunction "2_2") (pintype "passive"))
    )
    (net (code "37") (name "Net-(Q5-E)") (class "Default")
      (node (ref "C12") (pin "-") (pinfunction "-_-") (pintype "passive"))
      (node (ref "Q5") (pin "3") (pinfunction "E_3") (pintype "passive"))
      (node (ref "R12") (pin "2") (pinfunction "2_2") (pintype "passive"))
    )
    (net (code "38") (name "Net-(Q6-D)") (class "Default")
      (node (ref "C15") (pin "-") (pinfunction "-_-") (pintype "passive"))
      (node (ref "Q6") (pin "3") (pinfunction "D_3") (pintype "passive"))
      (node (ref "R17") (pin "2") (pinfunction "2_2") (pintype "passive"))
    )
    (net (code "39") (name "Net-(Q6-G)") (class "Default")
      (node (ref "D5") (pin "A") (pinfunction "A_A") (pintype "passive"))
      (node (ref "Q6") (pin "1") (pinfunction "G_1") (pintype "passive"))
    )
    (net (code "40") (name "Net-(Q6-S)") (class "Default")
      (node (ref "C18") (pin "2") (pinfunction "2_2") (pintype "passive"))
      (node (ref "Q6") (pin "2") (pinfunction "S_2") (pintype "passive"))
      (node (ref "R22") (pin "2") (pinfunction "2_2") (pintype "passive"))
    )
    (net (code "41") (name "Net-(Q7-B)") (class "Default")
      (node (ref "C16") (pin "2") (pinfunction "2_2") (pintype "passive"))
      (node (ref "Q7") (pin "2") (pinfunction "B_2") (pintype "passive"))
      (node (ref "R10") (pin "2") (pinfunction "2_2") (pintype "passive"))
    )
    (net (code "42") (name "Net-(Q7-E)") (class "Default")
      (node (ref "Q7") (pin "3") (pinfunction "E_3") (pintype "passive"))
      (node (ref "R20") (pin "2") (pinfunction "2_2") (pintype "passive"))
      (node (ref "R21") (pin "1") (pinfunction "1_1") (pintype "passive"))
    )
    (net (code "43") (name "Net-(Q8-D)") (class "Default")
      (node (ref "C12") (pin "+") (pinfunction "+_+") (pintype "passive"))
      (node (ref "Q8") (pin "3") (pinfunction "D_3") (pintype "passive"))
      (node (ref "R14") (pin "2") (pinfunction "2_2") (pintype "passive"))
    )
    (net (code "44") (name "Net-(Q8-G)") (class "Default")
      (node (ref "D6") (pin "A") (pinfunction "A_A") (pintype "passive"))
      (node (ref "Q8") (pin "1") (pinfunction "G_1") (pintype "passive"))
    )
    (net (code "45") (name "Net-(Q9-C)") (class "Default")
      (node (ref "C21") (pin "1") (pinfunction "1_1") (pintype "passive"))
      (node (ref "C23") (pin "1") (pinfunction "1_1") (pintype "passive"))
      (node (ref "C26") (pin "2") (pinfunction "2_2") (pintype "passive"))
      (node (ref "Q9") (pin "1") (pinfunction "C_1") (pintype "passive"))
      (node (ref "R32") (pin "2") (pinfunction "2_2") (pintype "passive"))
      (node (ref "R38") (pin "1") (pinfunction "1_1") (pintype "passive"))
      (node (ref "VR1") (pin "2") (pinfunction "2_2") (pintype "passive"))
      (node (ref "VR1") (pin "3") (pinfunction "3_3") (pintype "passive"))
    )
    (net (code "46") (name "Net-(Q10-D)") (class "Default")
      (node (ref "C21") (pin "2") (pinfunction "2_2") (pintype "passive"))
      (node (ref "Q10") (pin "3") (pinfunction "D_3") (pintype "passive"))
      (node (ref "Q9") (pin "2") (pinfunction "B_2") (pintype "passive"))
      (node (ref "R28") (pin "1") (pinfunction "1_1") (pintype "passive"))
    )
    (net (code "47") (name "Net-(Q10-G)") (class "Default")
      (node (ref "C18") (pin "1") (pinfunction "1_1") (pintype "passive"))
      (node (ref "Q10") (pin "1") (pinfunction "G_1") (pintype "passive"))
      (node (ref "R23") (pin "2") (pinfunction "2_2") (pintype "passive"))
    )
    (net (code "48") (name "Net-(Q10-S)") (class "Default")
      (node (ref "Q10") (pin "2") (pinfunction "S_2") (pintype "passive"))
      (node (ref "Q11") (pin "2") (pinfunction "S_2") (pintype "passive"))
      (node (ref "R30") (pin "2") (pinfunction "2_2") (pintype "passive"))
    )
    (net (code "49") (name "Net-(Q11-G)") (class "Default")
      (node (ref "C23") (pin "2") (pinfunction "2_2") (pintype "passive"))
      (node (ref "Q11") (pin "1") (pinfunction "G_1") (pintype "passive"))
      (node (ref "R29") (pin "1") (pinfunction "1_1") (pintype "passive"))
      (node (ref "R31") (pin "2") (pinfunction "2_2") (pintype "passive"))
    )
    (net (code "50") (name "Net-(Q12-B)") (class "Default")
      (node (ref "C20") (pin "2") (pinfunction "2_2") (pintype "passive"))
      (node (ref "Q12") (pin "2") (pinfunction "B_2") (pintype "passive"))
      (node (ref "Q14") (pin "3") (pinfunction "D_3") (pintype "passive"))
      (node (ref "R33") (pin "1") (pinfunction "1_1") (pintype "passive"))
    )
    (net (code "51") (name "Net-(Q12-C)") (class "Default")
      (node (ref "C17") (pin "2") (pinfunction "2_2") (pintype "passive"))
      (node (ref "C20") (pin "1") (pinfunction "1_1") (pintype "passive"))
      (node (ref "C25") (pin "1") (pinfunction "1_1") (pintype "passive"))
      (node (ref "Q12") (pin "1") (pinfunction "C_1") (pintype "passive"))
      (node (ref "R25") (pin "2") (pinfunction "2_2") (pintype "passive"))
      (node (ref "R26") (pin "1") (pinfunction "1_1") (pintype "passive"))
      (node (ref "VR1") (pin "5") (pinfunction "2_5") (pintype "passive"))
      (node (ref "VR1") (pin "6") (pinfunction "3_6") (pintype "passive"))
    )
    (net (code "52") (name "Net-(Q13-G)") (class "Default")
      (node (ref "C25") (pin "2") (pinfunction "2_2") (pintype "passive"))
      (node (ref "Q13") (pin "1") (pinfunction "G_1") (pintype "passive"))
      (node (ref "R27") (pin "1") (pinfunction "1_1") (pintype "passive"))
      (node (ref "R34") (pin "2") (pinfunction "2_2") (pintype "passive"))
    )
    (net (code "53") (name "Net-(Q13-S)") (class "Default")
      (node (ref "Q13") (pin "2") (pinfunction "S_2") (pintype "passive"))
      (node (ref "Q14") (pin "2") (pinfunction "S_2") (pintype "passive"))
      (node (ref "R36") (pin "2") (pinfunction "2_2") (pintype "passive"))
    )
    (net (code "54") (name "Net-(Q14-G)") (class "Default")
      (node (ref "C27") (pin "1") (pinfunction "1_1") (pintype "passive"))
      (node (ref "Q14") (pin "1") (pinfunction "G_1") (pintype "passive"))
      (node (ref "R35") (pin "2") (pinfunction "2_2") (pintype "passive"))
    )
    (net (code "55") (name "Net-(Q15-B)") (class "Default")
      (node (ref "C29") (pin "2") (pinfunction "2_2") (pintype "passive"))
      (node (ref "C30") (pin "1") (pinfunction "1_1") (pintype "passive"))
      (node (ref "Q15") (pin "2") (pinfunction "B_2") (pintype "passive"))
      (node (ref "R44") (pin "1") (pinfunction "1_1") (pintype "passive"))
      (node (ref "R45") (pin "2") (pinfunction "2_2") (pintype "passive"))
    )
    (net (code "56") (name "Net-(Q15-C)") (class "Default")
      (node (ref "C31") (pin "2") (pinfunction "2_2") (pintype "passive"))
      (node (ref "Q15") (pin "1") (pinfunction "C_1") (pintype "passive"))
      (node (ref "R41") (pin "2") (pinfunction "2_2") (pintype "passive"))
      (node (ref "R43") (pin "1") (pinfunction "1_1") (pintype "passive"))
      (node (ref "R47") (pin "1") (pinfunction "1_1") (pintype "passive"))
    )
    (net (code "57") (name "Net-(Q16-B)") (class "Default")
      (node (ref "C31") (pin "1") (pinfunction "1_1") (pintype "passive"))
      (node (ref "C32") (pin "1") (pinfunction "1_1") (pintype "passive"))
      (node (ref "Q16") (pin "2") (pinfunction "B_2") (pintype "passive"))
      (node (ref "R47") (pin "2") (pinfunction "2_2") (pintype "passive"))
      (node (ref "R48") (pin "2") (pinfunction "2_2") (pintype "passive"))
    )
    (net (code "58") (name "Net-(Q16-C)") (class "Default")
      (node (ref "C29") (pin "1") (pinfunction "1_1") (pintype "passive"))
      (node (ref "D11") (pin "A") (pinfunction "A_A") (pintype "passive"))
      (node (ref "Q16") (pin "1") (pinfunction "C_1") (pintype "passive"))
      (node (ref "R40") (pin "1") (pinfunction "1_1") (pintype "passive"))
      (node (ref "R44") (pin "2") (pinfunction "2_2") (pintype "passive"))
      (node (ref "R52") (pin "2") (pinfunction "2_2") (pintype "passive"))
    )
    (net (code "59") (name "Net-(R29-Pad2)") (class "Default")
      (node (ref "R29") (pin "2") (pinfunction "2_2") (pintype "passive"))
      (node (ref "VR1") (pin "1") (pinfunction "1_1") (pintype "passive"))
    )
    (net (code "60") (name "Net-(SW1-P)") (class "Default")
      (node (ref "R42") (pin "2") (pinfunction "2_2") (pintype "passive"))
      (node (ref "SW1") (pin "1") (pinfunction "P_1") (pintype "passive"))
    )
    (net (code "61") (name "Net-(VR1B-1)") (class "Default")
      (node (ref "R27") (pin "2") (pinfunction "2_2") (pintype "passive"))
      (node (ref "VR1") (pin "4") (pinfunction "1_4") (pintype "passive"))
    )
    (net (code "62") (name "Net-(VR2-Pad2)") (class "Default")
      (node (ref "VR2") (pin "2") (pinfunction "2_2") (pintype "passive"))
      (node (ref "VR3") (pin "3") (pinfunction "3_3") (pintype "passive"))
    )
    (net (code "63") (name "OUT") (class "Default")
      (node (ref "R1") (pin "2") (pinfunction "2_2") (pintype "passive"))
    )
    (net (code "64") (name "VA") (class "Default")
      (node (ref "C5") (pin "+") (pinfunction "+_+") (pintype "passive"))
      (node (ref "IC1") (pin "8") (pinfunction "V+_8") (pintype "power_in"))
      (node (ref "Q1") (pin "1") (pinfunction "C_1") (pintype "passive"))
      (node (ref "Q11") (pin "3") (pinfunction "D_3") (pintype "passive"))
      (node (ref "Q12") (pin "3") (pinfunction "E_3") (pintype "passive"))
      (node (ref "Q13") (pin "3") (pinfunction "D_3") (pintype "passive"))
      (node (ref "Q2") (pin "3") (pinfunction "E_3") (pintype "passive"))
      (node (ref "Q3") (pin "3") (pinfunction "D_3") (pintype "passive"))
      (node (ref "Q5") (pin "1") (pinfunction "C_1") (pintype "passive"))
      (node (ref "Q7") (pin "1") (pinfunction "C_1") (pintype "passive"))
      (node (ref "Q9") (pin "3") (pinfunction "E_3") (pintype "passive"))
      (node (ref "R28") (pin "2") (pinfunction "2_2") (pintype "passive"))
      (node (ref "R33") (pin "2") (pinfunction "2_2") (pintype "passive"))
      (node (ref "R5") (pin "2") (pinfunction "2_2") (pintype "passive"))
    )
    (net (code "65") (name "VB") (class "Default")
      (node (ref "C11") (pin "+") (pinfunction "+_+") (pintype "passive"))
      (node (ref "IC1") (pin "1") (pinfunction "OUT_1") (pintype "output"))
      (node (ref "IC1") (pin "2") (pinfunction "-IN_2") (pintype "input"))
      (node (ref "R10") (pin "1") (pinfunction "1_1") (pintype "passive"))
      (node (ref "R11") (pin "1") (pinfunction "1_1") (pintype "passive"))
      (node (ref "R13") (pin "1") (pinfunction "1_1") (pintype "passive"))
      (node (ref "R14") (pin "1") (pinfunction "1_1") (pintype "passive"))
      (node (ref "R15") (pin "1") (pinfunction "1_1") (pintype "passive"))
      (node (ref "R16") (pin "1") (pinfunction "1_1") (pintype "passive"))
      (node (ref "R17") (pin "1") (pinfunction "1_1") (pintype "passive"))
      (node (ref "R22") (pin "1") (pinfunction "1_1") (pintype "passive"))
      (node (ref "R23") (pin "1") (pinfunction "1_1") (pintype "passive"))
      (node (ref "R35") (pin "1") (pinfunction "1_1") (pintype "passive"))
      (node (ref "R7") (pin "1") (pinfunction "1_1") (pintype "passive"))
      (node (ref "R8") (pin "1") (pinfunction "1_1") (pintype "passive"))
    )
  )
)
